# Top.net
KiCad netlist of a schematic drawn in Altium Designer
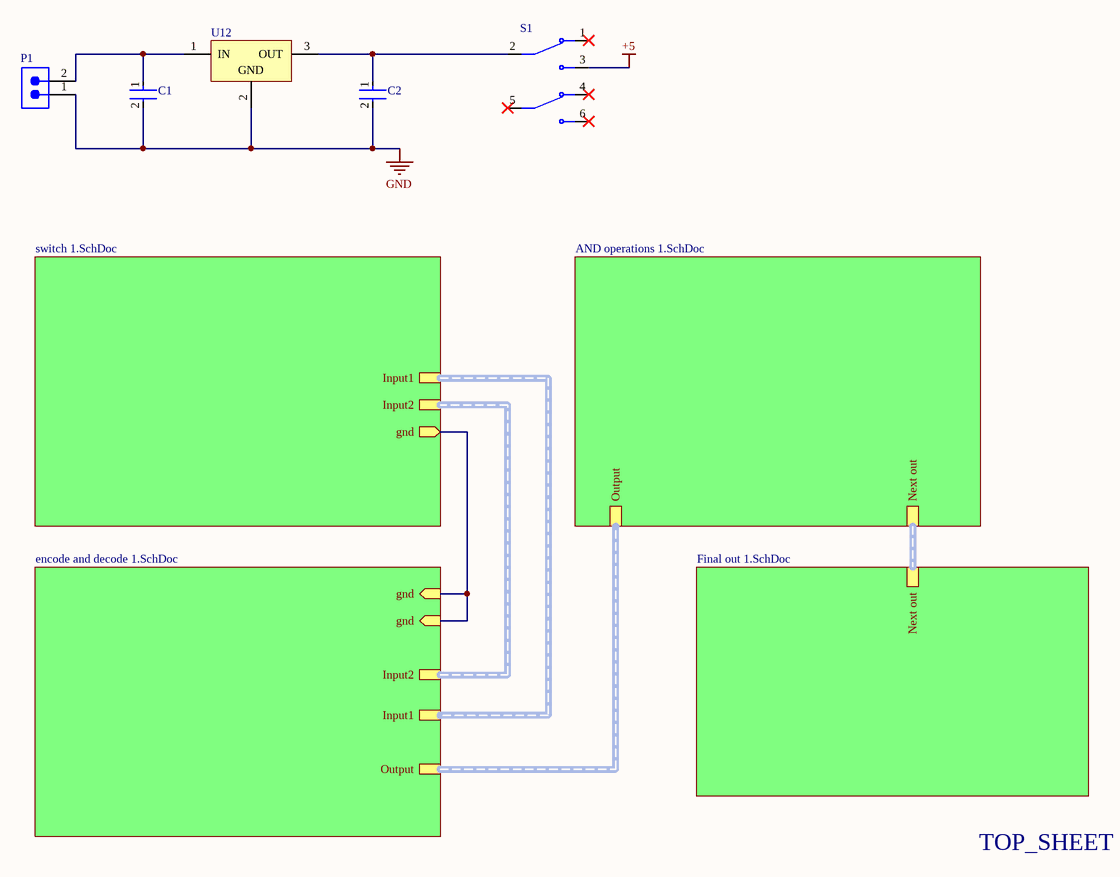
[diagram p0: Top.SchDoc]

(export (version "E")
  (design (tool "Eeschema 10.0.6"))
  (components
    (comp (ref "C1")
      (value "D222K33Y5PL6UJ5R")
      (footprint "FP-D222K33Y5PL6UJ5R-MFG")
      (description "CAP CER 2200PF 500V Y5P RADIAL")
      (fields (field (name "TOLERANCE") "10%"))
      (libsource (lib "Altium Content Vault") (part "02cd4be3c70576c341d710602a673aa"))
    )
    (comp (ref "C2")
      (value "D222K33Y5PL6UJ5R")
      (footprint "FP-D222K33Y5PL6UJ5R-MFG")
      (description "CAP CER 2200PF 500V Y5P RADIAL")
      (fields (field (name "TOLERANCE") "10%"))
      (libsource (lib "Altium Content Vault") (part "02cd4be3c70576c341d710602a673aa"))
    )
    (comp (ref "P1")
      (value "691311500002")
      (footprint "691311500002")
      (fields (field (name "VOLTAGE") "300V"))
      (libsource (lib "Altium Content Vault") (part "TBL - 1R - 02P - Male"))
    )
    (comp (ref "S1")
      (value "TL2230OAF140")
      (footprint "SW_TL2230OAF140")
      (description "Pushbutton Switch DPDT Standard Through Hole")
      (fields (field (name "MF") "E-Switch"))
      (libsource (lib "TL2230OAF140") (part "TL2230OAF140"))
    )
    (comp (ref "U12")
      (value "L7805CP")
      (footprint "TO220FP")
      (description "Positive Voltage Regulator, 5V, 3-Pin TO-220FP")
      (libsource (lib "Altium Content Vault") (part "PM-REG-L4940-SIL3"))
    )
  )
  (nets
    (net (code "1") (name "+5") (class "Default")
      (node (ref "S1") (pin "3") (pinfunction "NO1_3") (pintype "passive"))
    )
    (net (code "7") (name "GND") (class "Default")
      (node (ref "C1") (pin "2") (pinfunction "2_2") (pintype "passive"))
      (node (ref "C2") (pin "2") (pinfunction "2_2") (pintype "passive"))
      (node (ref "P1") (pin "1") (pinfunction "1_1") (pintype "passive"))
      (node (ref "U12") (pin "2") (pinfunction "GND_2") (pintype "power_in"))
    )
    (net (code "8") (name "Net-(S1-COM1)") (class "Default")
      (node (ref "C2") (pin "1") (pinfunction "1_1") (pintype "passive"))
      (node (ref "S1") (pin "2") (pinfunction "COM1_2") (pintype "passive"))
      (node (ref "U12") (pin "3") (pinfunction "OUT_3") (pintype "power_in"))
    )
    (net (code "9") (name "Net-(U12-IN)") (class "Default")
      (node (ref "C1") (pin "1") (pinfunction "1_1") (pintype "passive"))
      (node (ref "P1") (pin "2") (pinfunction "2_2") (pintype "passive"))
      (node (ref "U12") (pin "1") (pinfunction "IN_1") (pintype "power_in"))
    )
    (net (code "10") (name "unconnected-(S1-COM2-Pad5)") (class "Default")
      (node (ref "S1") (pin "5") (pinfunction "COM2_5") (pintype "passive+no_connect"))
    )
    (net (code "11") (name "unconnected-(S1-NC1-Pad1)") (class "Default")
      (node (ref "S1") (pin "1") (pinfunction "NC1_1") (pintype "passive+no_connect"))
    )
    (net (code "12") (name "unconnected-(S1-NC2-Pad4)") (class "Default")
      (node (ref "S1") (pin "4") (pinfunction "NC2_4") (pintype "passive+no_connect"))
    )
    (net (code "13") (name "unconnected-(S1-NO2-Pad6)") (class "Default")
      (node (ref "S1") (pin "6") (pinfunction "NO2_6") (pintype "passive+no_connect"))
    )
  )
)
